# PanelDue.net
KiCad netlist of a schematic drawn in EAGLE
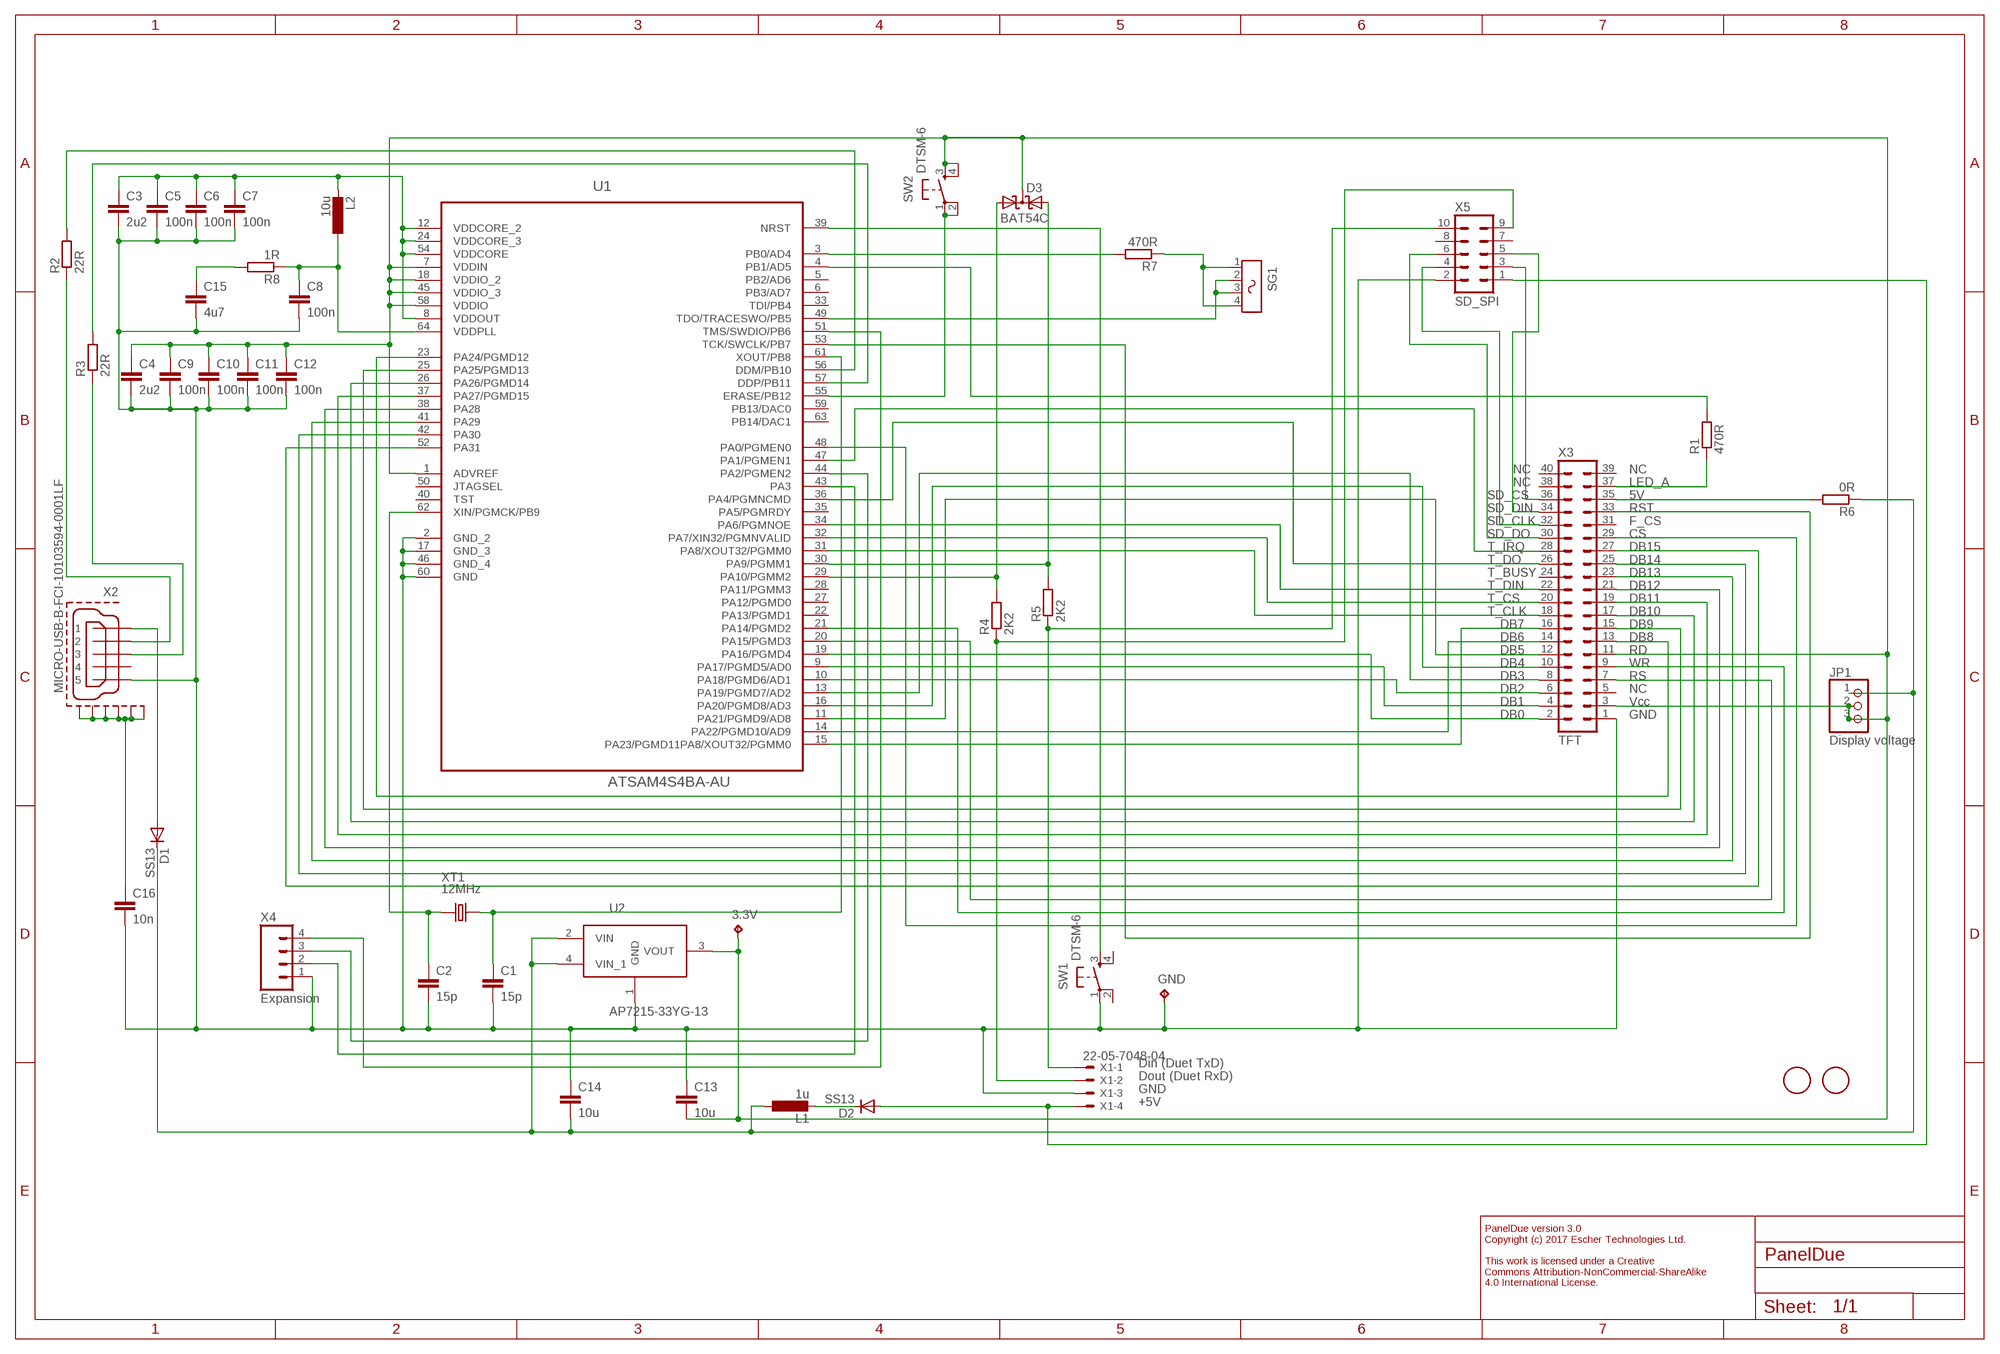
[diagram p0: schematic, sheet 1]

(export (version "E")
  (design (tool "Eeschema 10.0.6"))
  (components
    (comp (ref "3.3V")
      (value "TPPAD1-10")
      (footprint "eagle-import:P1-10")
      (libsource (lib "eagle-import") (part "TPPAD1-10"))
    )
    (comp (ref "C1")
      (value "15p")
      (footprint "eagle-import:C0603")
      (libsource (lib "eagle-import") (part "C-EUC0603"))
    )
    (comp (ref "C2")
      (value "15p")
      (footprint "eagle-import:C0603")
      (libsource (lib "eagle-import") (part "C-EUC0603"))
    )
    (comp (ref "C3")
      (value "2u2")
      (footprint "eagle-import:C0603")
      (libsource (lib "eagle-import") (part "C-EUC0603"))
    )
    (comp (ref "C4")
      (value "2u2")
      (footprint "eagle-import:C0603")
      (libsource (lib "eagle-import") (part "C-EUC0603"))
    )
    (comp (ref "C5")
      (value "100n")
      (footprint "eagle-import:C0603")
      (libsource (lib "eagle-import") (part "C-EUC0603"))
    )
    (comp (ref "C6")
      (value "100n")
      (footprint "eagle-import:C0603")
      (libsource (lib "eagle-import") (part "C-EUC0603"))
    )
    (comp (ref "C7")
      (value "100n")
      (footprint "eagle-import:C0603")
      (libsource (lib "eagle-import") (part "C-EUC0603"))
    )
    (comp (ref "C8")
      (value "100n")
      (footprint "eagle-import:C0603")
      (libsource (lib "eagle-import") (part "C-EUC0603"))
    )
    (comp (ref "C9")
      (value "100n")
      (footprint "eagle-import:C0603")
      (libsource (lib "eagle-import") (part "C-EUC0603"))
    )
    (comp (ref "C10")
      (value "100n")
      (footprint "eagle-import:C0603")
      (libsource (lib "eagle-import") (part "C-EUC0603"))
    )
    (comp (ref "C11")
      (value "100n")
      (footprint "eagle-import:C0603")
      (libsource (lib "eagle-import") (part "C-EUC0603"))
    )
    (comp (ref "C12")
      (value "100n")
      (footprint "eagle-import:C0603")
      (libsource (lib "eagle-import") (part "C-EUC0603"))
    )
    (comp (ref "C13")
      (value "10u")
      (footprint "eagle-import:C0805")
      (libsource (lib "eagle-import") (part "C-EUC0805"))
    )
    (comp (ref "C14")
      (value "10u")
      (footprint "eagle-import:C0805")
      (libsource (lib "eagle-import") (part "C-EUC0805"))
    )
    (comp (ref "C15")
      (value "4u7")
      (footprint "eagle-import:C0603")
      (libsource (lib "eagle-import") (part "C-EUC0603"))
    )
    (comp (ref "C16")
      (value "10n")
      (footprint "eagle-import:C0603")
      (libsource (lib "eagle-import") (part "C-EUC0603"))
    )
    (comp (ref "D1")
      (value "SS13")
      (footprint "eagle-import:DO214AC")
      (libsource (lib "eagle-import") (part "DIODE-DO214AC"))
    )
    (comp (ref "D2")
      (value "SS13")
      (footprint "eagle-import:DO214AC")
      (libsource (lib "eagle-import") (part "DIODE-DO214AC"))
    )
    (comp (ref "D3")
      (value "BAT54C")
      (footprint "eagle-import:SOT23")
      (libsource (lib "eagle-import") (part "BAT54C"))
    )
    (comp (ref "GND")
      (value "TPPAD1-10")
      (footprint "eagle-import:P1-10")
      (libsource (lib "eagle-import") (part "TPPAD1-10"))
    )
    (comp (ref "JP1")
      (value "Display voltage")
      (footprint "eagle-import:1X03")
      (libsource (lib "eagle-import") (part "PINHD-1X3"))
    )
    (comp (ref "L1")
      (value "1u")
      (footprint "eagle-import:L2012C")
      (libsource (lib "eagle-import") (part "L-EUL2012C"))
    )
    (comp (ref "L2")
      (value "10u")
      (footprint "eagle-import:L2012C")
      (libsource (lib "eagle-import") (part "L-EUL2012C"))
    )
    (comp (ref "R1")
      (value "470R")
      (footprint "eagle-import:R0603")
      (libsource (lib "eagle-import") (part "R-EU_R0603"))
    )
    (comp (ref "R2")
      (value "22R")
      (footprint "eagle-import:R0603")
      (libsource (lib "eagle-import") (part "R-EU_R0603"))
    )
    (comp (ref "R3")
      (value "22R")
      (footprint "eagle-import:R0603")
      (libsource (lib "eagle-import") (part "R-EU_R0603"))
    )
    (comp (ref "R4")
      (value "2K2")
      (footprint "eagle-import:R0603")
      (libsource (lib "eagle-import") (part "R-EU_R0603"))
    )
    (comp (ref "R5")
      (value "2K2")
      (footprint "eagle-import:R0603")
      (libsource (lib "eagle-import") (part "R-EU_R0603"))
    )
    (comp (ref "R6")
      (value "0R")
      (footprint "eagle-import:R0603")
      (libsource (lib "eagle-import") (part "R-EU_R0603"))
    )
    (comp (ref "R7")
      (value "470R")
      (footprint "eagle-import:R0603")
      (libsource (lib "eagle-import") (part "R-EU_R0603"))
    )
    (comp (ref "R8")
      (value "1R")
      (footprint "eagle-import:R0603")
      (libsource (lib "eagle-import") (part "R-EU_R0603"))
    )
    (comp (ref "SG1")
      (value "F/QMX2")
      (footprint "eagle-import:F_QMX2")
      (libsource (lib "eagle-import") (part "F/QMX2"))
    )
    (comp (ref "SW1")
      (value "DTSM-6")
      (footprint "eagle-import:DTSM-6")
      (libsource (lib "eagle-import") (part "DTSM-6"))
    )
    (comp (ref "SW2")
      (value "DTSM-6")
      (footprint "eagle-import:DTSM-6")
      (libsource (lib "eagle-import") (part "DTSM-6"))
    )
    (comp (ref "U$1")
      (value "FIDUCIAL")
      (footprint "eagle-import:FIDUCIAL_1MM")
      (libsource (lib "eagle-import") (part "FIDUCIAL"))
    )
    (comp (ref "U$2")
      (value "FIDUCIAL")
      (footprint "eagle-import:FIDUCIAL_1MM")
      (libsource (lib "eagle-import") (part "FIDUCIAL"))
    )
    (comp (ref "U1")
      (value "ATSAM4S4BA-AU")
      (footprint "eagle-import:QFP50P1200X1200X160-64N")
      (fields (field (name "MPN") "ATSAM3S2BA-AU"))
      (libsource (lib "eagle-import") (part "ATSAM3S2BA-AU"))
    )
    (comp (ref "U2")
      (value "AP7215-33YG-13")
      (footprint "eagle-import:SOT150P400X160-4N")
      (fields (field (name "MPN") "MCP1702T-3302E/MB"))
      (libsource (lib "eagle-import") (part "MCP17-MCP1702T-3302E/MB"))
    )
    (comp (ref "X1")
      (value "22-05-7048-04")
      (footprint "eagle-import:7395-04")
      (libsource (lib "eagle-import") (part "22-?-0405-7048"))
    )
    (comp (ref "X2")
      (value "MICRO-USB-B-FCI-10103594-0001LF")
      (footprint "eagle-import:10103594-0001LF")
      (libsource (lib "eagle-import") (part "MICRO-USB-B-FCI-10103594-0001LF"))
    )
    (comp (ref "X3")
      (value "TFT")
      (footprint "eagle-import:MA20-2")
      (libsource (lib "eagle-import") (part "MA20-2"))
    )
    (comp (ref "X4")
      (value "Expansion")
      (footprint "eagle-import:1X04")
      (libsource (lib "eagle-import") (part "M04PTH"))
    )
    (comp (ref "X5")
      (value "SD_SPI")
      (footprint "eagle-import:ML10L")
      (libsource (lib "eagle-import") (part "ML10L"))
    )
    (comp (ref "XT1")
      (value "12MHz")
      (footprint "eagle-import:CRYSTAL-SMD-2PIN-5X3.2")
      (libsource (lib "eagle-import") (part "CRYSTAL-SMD-2PIN-5X3.2"))
    )
  )
  (nets
    (net (code "1") (name "Net-(C15-Pad1)") (class "Default")
      (node (ref "C15") (pin "1") (pinfunction "1_1") (pintype "passive"))
      (node (ref "R8") (pin "2") (pinfunction "2_2") (pintype "passive"))
    )
    (net (code "2") (name "Net-(C16-Pad1)") (class "Default")
      (node (ref "C16") (pin "1") (pinfunction "1_1") (pintype "passive"))
      (node (ref "X2") (pin "GND1") (pinfunction "GND1_GND1") (pintype "bidirectional"))
      (node (ref "X2") (pin "GND2") (pinfunction "GND2_GND2") (pintype "bidirectional"))
      (node (ref "X2") (pin "GND3") (pinfunction "GND3_GND3") (pintype "bidirectional"))
      (node (ref "X2") (pin "GND4") (pinfunction "GND4_GND4") (pintype "bidirectional"))
      (node (ref "X2") (pin "GND5") (pinfunction "GND5_GND5") (pintype "bidirectional"))
      (node (ref "X2") (pin "GND6") (pinfunction "GND6_GND6") (pintype "bidirectional"))
    )
    (net (code "3") (name "Net-(D1-PadA)") (class "Default")
      (node (ref "D1") (pin "A") (pinfunction "A_A") (pintype "passive"))
      (node (ref "X2") (pin "1") (pinfunction "1_1") (pintype "input"))
    )
    (net (code "4") (name "Net-(D2-PadC)") (class "Default")
      (node (ref "D2") (pin "C") (pinfunction "C_C") (pintype "passive"))
      (node (ref "L1") (pin "2") (pinfunction "2_2") (pintype "passive"))
    )
    (net (code "5") (name "Net-(D3-A1)") (class "Default")
      (node (ref "D3") (pin "1") (pinfunction "A1_1") (pintype "passive"))
      (node (ref "R4") (pin "2") (pinfunction "2_2") (pintype "passive"))
      (node (ref "U1") (pin "29") (pinfunction "PA10/PGMM2_29") (pintype "bidirectional"))
    )
    (net (code "6") (name "Net-(D3-A2)") (class "Default")
      (node (ref "D3") (pin "2") (pinfunction "A2_2") (pintype "passive"))
      (node (ref "R5") (pin "2") (pinfunction "2_2") (pintype "passive"))
      (node (ref "U1") (pin "30") (pinfunction "PA9/PGMM1_30") (pintype "bidirectional"))
    )
    (net (code "7") (name "Net-(D3-CC)") (class "Default")
      (node (ref "3.3V") (pin "TP") (pinfunction "TP_TP") (pintype "input"))
      (node (ref "C10") (pin "1") (pinfunction "1_1") (pintype "passive"))
      (node (ref "C11") (pin "1") (pinfunction "1_1") (pintype "passive"))
      (node (ref "C12") (pin "1") (pinfunction "1_1") (pintype "passive"))
      (node (ref "C13") (pin "2") (pinfunction "2_2") (pintype "passive"))
      (node (ref "C4") (pin "1") (pinfunction "1_1") (pintype "passive"))
      (node (ref "C9") (pin "1") (pinfunction "1_1") (pintype "passive"))
      (node (ref "D3") (pin "3") (pinfunction "CC_3") (pintype "passive"))
      (node (ref "JP1") (pin "2") (pinfunction "2_2") (pintype "passive"))
      (node (ref "JP1") (pin "3") (pinfunction "3_3") (pintype "passive"))
      (node (ref "SW2") (pin "3") (pinfunction "3_3") (pintype "passive"))
      (node (ref "SW2") (pin "4") (pinfunction "4_4") (pintype "passive"))
      (node (ref "U1") (pin "1") (pinfunction "ADVREF_1") (pintype "input"))
      (node (ref "U1") (pin "18") (pinfunction "VDDIO_2_18") (pintype "power_in"))
      (node (ref "U1") (pin "45") (pinfunction "VDDIO_3_45") (pintype "power_in"))
      (node (ref "U1") (pin "58") (pinfunction "VDDIO_58") (pintype "power_in"))
      (node (ref "U1") (pin "7") (pinfunction "VDDIN_7") (pintype "power_in"))
      (node (ref "U2") (pin "3") (pinfunction "VOUT_3") (pintype "output"))
      (node (ref "X3") (pin "11") (pinfunction "11_11") (pintype "passive"))
      (node (ref "X3") (pin "3") (pinfunction "3_3") (pintype "passive"))
    )
    (net (code "8") (name "Net-(R1-Pad1)") (class "Default")
      (node (ref "R1") (pin "1") (pinfunction "1_1") (pintype "passive"))
      (node (ref "X3") (pin "37") (pinfunction "37_37") (pintype "passive"))
    )
    (net (code "9") (name "Net-(R2-Pad1)") (class "Default")
      (node (ref "R2") (pin "1") (pinfunction "1_1") (pintype "passive"))
      (node (ref "X2") (pin "2") (pinfunction "2_2") (pintype "input"))
    )
    (net (code "10") (name "Net-(R3-Pad1)") (class "Default")
      (node (ref "R3") (pin "1") (pinfunction "1_1") (pintype "passive"))
      (node (ref "X2") (pin "3") (pinfunction "3_3") (pintype "input"))
    )
    (net (code "11") (name "Net-(R6-Pad2)") (class "Default")
      (node (ref "R6") (pin "2") (pinfunction "2_2") (pintype "passive"))
      (node (ref "X3") (pin "35") (pinfunction "35_35") (pintype "passive"))
    )
    (net (code "12") (name "Net-(SG1-P$1)") (class "Default")
      (node (ref "R7") (pin "1") (pinfunction "1_1") (pintype "passive"))
      (node (ref "SG1") (pin "1") (pinfunction "P$1_1") (pintype "input"))
      (node (ref "SG1") (pin "4") (pinfunction "P$4_4") (pintype "input"))
    )
    (net (code "13") (name "Net-(SG1-P$2)") (class "Default")
      (node (ref "SG1") (pin "2") (pinfunction "P$2_2") (pintype "input"))
      (node (ref "SG1") (pin "3") (pinfunction "P$3_3") (pintype "input"))
      (node (ref "U1") (pin "49") (pinfunction "TDO/TRACESWO/PB5_49") (pintype "bidirectional"))
    )
    (net (code "14") (name "Net-(U1-DDM{slash}PB10)") (class "Default")
      (node (ref "R2") (pin "2") (pinfunction "2_2") (pintype "passive"))
      (node (ref "U1") (pin "56") (pinfunction "DDM/PB10_56") (pintype "bidirectional"))
    )
    (net (code "15") (name "Net-(U1-DDP{slash}PB11)") (class "Default")
      (node (ref "R3") (pin "2") (pinfunction "2_2") (pintype "passive"))
      (node (ref "U1") (pin "57") (pinfunction "DDP/PB11_57") (pintype "bidirectional"))
    )
    (net (code "16") (name "Net-(U1-ERASE{slash}PB12)") (class "Default")
      (node (ref "SW2") (pin "1") (pinfunction "1_1") (pintype "passive"))
      (node (ref "SW2") (pin "2") (pinfunction "2_2") (pintype "passive"))
      (node (ref "U1") (pin "55") (pinfunction "ERASE/PB12_55") (pintype "bidirectional"))
    )
    (net (code "17") (name "Net-(U1-GND)") (class "Default")
      (node (ref "C1") (pin "2") (pinfunction "2_2") (pintype "passive"))
      (node (ref "C10") (pin "2") (pinfunction "2_2") (pintype "passive"))
      (node (ref "C11") (pin "2") (pinfunction "2_2") (pintype "passive"))
      (node (ref "C12") (pin "2") (pinfunction "2_2") (pintype "passive"))
      (node (ref "C13") (pin "1") (pinfunction "1_1") (pintype "passive"))
      (node (ref "C14") (pin "1") (pinfunction "1_1") (pintype "passive"))
      (node (ref "C15") (pin "2") (pinfunction "2_2") (pintype "passive"))
      (node (ref "C16") (pin "2") (pinfunction "2_2") (pintype "passive"))
      (node (ref "C2") (pin "2") (pinfunction "2_2") (pintype "passive"))
      (node (ref "C3") (pin "2") (pinfunction "2_2") (pintype "passive"))
      (node (ref "C4") (pin "2") (pinfunction "2_2") (pintype "passive"))
      (node (ref "C5") (pin "2") (pinfunction "2_2") (pintype "passive"))
      (node (ref "C6") (pin "2") (pinfunction "2_2") (pintype "passive"))
      (node (ref "C7") (pin "2") (pinfunction "2_2") (pintype "passive"))
      (node (ref "C8") (pin "2") (pinfunction "2_2") (pintype "passive"))
      (node (ref "C9") (pin "2") (pinfunction "2_2") (pintype "passive"))
      (node (ref "GND") (pin "TP") (pinfunction "TP_TP") (pintype "input"))
      (node (ref "SW1") (pin "1") (pinfunction "1_1") (pintype "passive"))
      (node (ref "U1") (pin "17") (pinfunction "GND_3_17") (pintype "passive"))
      (node (ref "U1") (pin "2") (pinfunction "GND_2_2") (pintype "passive"))
      (node (ref "U1") (pin "46") (pinfunction "GND_4_46") (pintype "passive"))
      (node (ref "U1") (pin "60") (pinfunction "GND_60") (pintype "passive"))
      (node (ref "U2") (pin "1") (pinfunction "GND_1") (pintype "power_in"))
      (node (ref "X1") (pin "3") (pinfunction "S_3") (pintype "passive"))
      (node (ref "X2") (pin "5") (pinfunction "5_5") (pintype "input"))
      (node (ref "X3") (pin "1") (pinfunction "1_1") (pintype "passive"))
      (node (ref "X4") (pin "1") (pinfunction "1_1") (pintype "passive"))
      (node (ref "X5") (pin "2") (pinfunction "2_2") (pintype "passive"))
    )
    (net (code "18") (name "Net-(U1-NRST)") (class "Default")
      (node (ref "SW1") (pin "3") (pinfunction "3_3") (pintype "passive"))
      (node (ref "U1") (pin "39") (pinfunction "NRST_39") (pintype "bidirectional"))
    )
    (net (code "19") (name "Net-(U1-PA0{slash}PGMEN0)") (class "Default")
      (node (ref "U1") (pin "48") (pinfunction "PA0/PGMEN0_48") (pintype "bidirectional"))
      (node (ref "X3") (pin "29") (pinfunction "29_29") (pintype "passive"))
    )
    (net (code "20") (name "Net-(U1-PA1{slash}PGMEN1)") (class "Default")
      (node (ref "U1") (pin "47") (pinfunction "PA1/PGMEN1_47") (pintype "bidirectional"))
      (node (ref "X3") (pin "28") (pinfunction "28_28") (pintype "passive"))
    )
    (net (code "21") (name "Net-(U1-PA2{slash}PGMEN2)") (class "Default")
      (node (ref "U1") (pin "44") (pinfunction "PA2/PGMEN2_44") (pintype "bidirectional"))
      (node (ref "X4") (pin "3") (pinfunction "3_3") (pintype "passive"))
    )
    (net (code "22") (name "Net-(U1-PA3)") (class "Default")
      (node (ref "U1") (pin "43") (pinfunction "PA3_43") (pintype "bidirectional"))
      (node (ref "X4") (pin "2") (pinfunction "2_2") (pintype "passive"))
    )
    (net (code "23") (name "Net-(U1-PA4{slash}PGMNCMD)") (class "Default")
      (node (ref "U1") (pin "36") (pinfunction "PA4/PGMNCMD_36") (pintype "bidirectional"))
      (node (ref "X3") (pin "26") (pinfunction "26_26") (pintype "passive"))
    )
    (net (code "24") (name "Net-(U1-PA6{slash}PGMNOE)") (class "Default")
      (node (ref "U1") (pin "34") (pinfunction "PA6/PGMNOE_34") (pintype "bidirectional"))
      (node (ref "X3") (pin "22") (pinfunction "22_22") (pintype "passive"))
    )
    (net (code "25") (name "Net-(U1-PA7{slash}XIN32{slash}PGMNVALID)") (class "Default")
      (node (ref "U1") (pin "32") (pinfunction "PA7/XIN32/PGMNVALID_32") (pintype "bidirectional"))
      (node (ref "X3") (pin "20") (pinfunction "20_20") (pintype "passive"))
    )
    (net (code "26") (name "Net-(U1-PA8{slash}XOUT32{slash}PGMM0)") (class "Default")
      (node (ref "U1") (pin "31") (pinfunction "PA8/XOUT32/PGMM0_31") (pintype "bidirectional"))
      (node (ref "X3") (pin "18") (pinfunction "18_18") (pintype "passive"))
    )
    (net (code "27") (name "Net-(U1-PA14{slash}PGMD2)") (class "Default")
      (node (ref "U1") (pin "21") (pinfunction "PA14/PGMD2_21") (pintype "bidirectional"))
      (node (ref "X3") (pin "9") (pinfunction "9_9") (pintype "passive"))
    )
    (net (code "28") (name "Net-(U1-PA15{slash}PGMD3)") (class "Default")
      (node (ref "U1") (pin "20") (pinfunction "PA15/PGMD3_20") (pintype "bidirectional"))
      (node (ref "X3") (pin "7") (pinfunction "7_7") (pintype "passive"))
    )
    (net (code "29") (name "Net-(U1-PA16{slash}PGMD4)") (class "Default")
      (node (ref "U1") (pin "19") (pinfunction "PA16/PGMD4_19") (pintype "bidirectional"))
      (node (ref "X3") (pin "2") (pinfunction "2_2") (pintype "passive"))
    )
    (net (code "30") (name "Net-(U1-PA17{slash}PGMD5{slash}AD0)") (class "Default")
      (node (ref "U1") (pin "9") (pinfunction "PA17/PGMD5/AD0_9") (pintype "bidirectional"))
      (node (ref "X3") (pin "4") (pinfunction "4_4") (pintype "passive"))
    )
    (net (code "31") (name "Net-(U1-PA18{slash}PGMD6{slash}AD1)") (class "Default")
      (node (ref "U1") (pin "10") (pinfunction "PA18/PGMD6/AD1_10") (pintype "bidirectional"))
      (node (ref "X3") (pin "6") (pinfunction "6_6") (pintype "passive"))
    )
    (net (code "32") (name "Net-(U1-PA19{slash}PGMD7{slash}AD2)") (class "Default")
      (node (ref "U1") (pin "13") (pinfunction "PA19/PGMD7/AD2_13") (pintype "bidirectional"))
      (node (ref "X3") (pin "8") (pinfunction "8_8") (pintype "passive"))
    )
    (net (code "33") (name "Net-(U1-PA20{slash}PGMD8{slash}AD3)") (class "Default")
      (node (ref "U1") (pin "16") (pinfunction "PA20/PGMD8/AD3_16") (pintype "bidirectional"))
      (node (ref "X3") (pin "10") (pinfunction "10_10") (pintype "passive"))
    )
    (net (code "34") (name "Net-(U1-PA21{slash}PGMD9{slash}AD8)") (class "Default")
      (node (ref "U1") (pin "11") (pinfunction "PA21/PGMD9/AD8_11") (pintype "bidirectional"))
      (node (ref "X3") (pin "12") (pinfunction "12_12") (pintype "passive"))
    )
    (net (code "35") (name "Net-(U1-PA22{slash}PGMD10{slash}AD9)") (class "Default")
      (node (ref "U1") (pin "14") (pinfunction "PA22/PGMD10/AD9_14") (pintype "bidirectional"))
      (node (ref "X3") (pin "14") (pinfunction "14_14") (pintype "passive"))
    )
    (net (code "36") (name "Net-(U1-PA23{slash}PGMD11PA8{slash}XOUT32{slash}PGMM0)") (class "Default")
      (node (ref "U1") (pin "15") (pinfunction "PA23/PGMD11PA8/XOUT32/PGMM0_15") (pintype "bidirectional"))
      (node (ref "X3") (pin "16") (pinfunction "16_16") (pintype "passive"))
    )
    (net (code "37") (name "Net-(U1-PA24{slash}PGMD12)") (class "Default")
      (node (ref "U1") (pin "23") (pinfunction "PA24/PGMD12_23") (pintype "bidirectional"))
      (node (ref "X3") (pin "13") (pinfunction "13_13") (pintype "passive"))
    )
    (net (code "38") (name "Net-(U1-PA25{slash}PGMD13)") (class "Default")
      (node (ref "U1") (pin "25") (pinfunction "PA25/PGMD13_25") (pintype "bidirectional"))
      (node (ref "X3") (pin "15") (pinfunction "15_15") (pintype "passive"))
    )
    (net (code "39") (name "Net-(U1-PA26{slash}PGMD14)") (class "Default")
      (node (ref "U1") (pin "26") (pinfunction "PA26/PGMD14_26") (pintype "bidirectional"))
      (node (ref "X3") (pin "17") (pinfunction "17_17") (pintype "passive"))
    )
    (net (code "40") (name "Net-(U1-PA27{slash}PGMD15)") (class "Default")
      (node (ref "U1") (pin "37") (pinfunction "PA27/PGMD15_37") (pintype "bidirectional"))
      (node (ref "X3") (pin "19") (pinfunction "19_19") (pintype "passive"))
    )
    (net (code "41") (name "Net-(U1-PA28)") (class "Default")
      (node (ref "U1") (pin "38") (pinfunction "PA28_38") (pintype "bidirectional"))
      (node (ref "X3") (pin "21") (pinfunction "21_21") (pintype "passive"))
    )
    (net (code "42") (name "Net-(U1-PA29)") (class "Default")
      (node (ref "U1") (pin "41") (pinfunction "PA29_41") (pintype "bidirectional"))
      (node (ref "X3") (pin "23") (pinfunction "23_23") (pintype "passive"))
    )
    (net (code "43") (name "Net-(U1-PA30)") (class "Default")
      (node (ref "U1") (pin "42") (pinfunction "PA30_42") (pintype "bidirectional"))
      (node (ref "X3") (pin "25") (pinfunction "25_25") (pintype "passive"))
    )
    (net (code "44") (name "Net-(U1-PA31)") (class "Default")
      (node (ref "U1") (pin "52") (pinfunction "PA31_52") (pintype "bidirectional"))
      (node (ref "X3") (pin "27") (pinfunction "27_27") (pintype "passive"))
    )
    (net (code "45") (name "Net-(U1-PB0{slash}AD4)") (class "Default")
      (node (ref "R7") (pin "2") (pinfunction "2_2") (pintype "passive"))
      (node (ref "U1") (pin "3") (pinfunction "PB0/AD4_3") (pintype "bidirectional"))
    )
    (net (code "46") (name "Net-(U1-PB1{slash}AD5)") (class "Default")
      (node (ref "R1") (pin "2") (pinfunction "2_2") (pintype "passive"))
      (node (ref "U1") (pin "4") (pinfunction "PB1/AD5_4") (pintype "bidirectional"))
    )
    (net (code "47") (name "Net-(U1-TCK{slash}SWCLK{slash}PB7)") (class "Default")
      (node (ref "U1") (pin "53") (pinfunction "TCK/SWCLK/PB7_53") (pintype "bidirectional"))
      (node (ref "X3") (pin "33") (pinfunction "33_33") (pintype "passive"))
    )
    (net (code "48") (name "Net-(U1-TMS{slash}SWDIO{slash}PB6)") (class "Default")
      (node (ref "U1") (pin "51") (pinfunction "TMS/SWDIO/PB6_51") (pintype "bidirectional"))
      (node (ref "X4") (pin "4") (pinfunction "4_4") (pintype "passive"))
    )
    (net (code "49") (name "Net-(U1-VDDCORE)") (class "Default")
      (node (ref "C3") (pin "1") (pinfunction "1_1") (pintype "passive"))
      (node (ref "C5") (pin "1") (pinfunction "1_1") (pintype "passive"))
      (node (ref "C6") (pin "1") (pinfunction "1_1") (pintype "passive"))
      (node (ref "C7") (pin "1") (pinfunction "1_1") (pintype "passive"))
      (node (ref "L2") (pin "2") (pinfunction "2_2") (pintype "passive"))
      (node (ref "U1") (pin "12") (pinfunction "VDDCORE_2_12") (pintype "power_in"))
      (node (ref "U1") (pin "24") (pinfunction "VDDCORE_3_24") (pintype "power_in"))
      (node (ref "U1") (pin "54") (pinfunction "VDDCORE_54") (pintype "power_in"))
      (node (ref "U1") (pin "8") (pinfunction "VDDOUT_8") (pintype "power_in"))
    )
    (net (code "50") (name "Net-(U1-VDDPLL)") (class "Default")
      (node (ref "C8") (pin "1") (pinfunction "1_1") (pintype "passive"))
      (node (ref "L2") (pin "1") (pinfunction "1_1") (pintype "passive"))
      (node (ref "R8") (pin "1") (pinfunction "1_1") (pintype "passive"))
      (node (ref "U1") (pin "64") (pinfunction "VDDPLL_64") (pintype "power_in"))
    )
    (net (code "51") (name "Net-(U1-XIN{slash}PGMCK{slash}PB9)") (class "Default")
      (node (ref "C2") (pin "1") (pinfunction "1_1") (pintype "passive"))
      (node (ref "U1") (pin "62") (pinfunction "XIN/PGMCK/PB9_62") (pintype "input"))
      (node (ref "XT1") (pin "P$1") (pinfunction "1_P$1") (pintype "passive"))
    )
    (net (code "52") (name "Net-(U1-XOUT{slash}PB8)") (class "Default")
      (node (ref "C1") (pin "1") (pinfunction "1_1") (pintype "passive"))
      (node (ref "U1") (pin "61") (pinfunction "XOUT/PB8_61") (pintype "output"))
      (node (ref "XT1") (pin "P$2") (pinfunction "2_P$2") (pintype "passive"))
    )
    (net (code "53") (name "Net-(U2-VIN)") (class "Default")
      (node (ref "C14") (pin "2") (pinfunction "2_2") (pintype "passive"))
      (node (ref "D1") (pin "C") (pinfunction "C_C") (pintype "passive"))
      (node (ref "JP1") (pin "1") (pinfunction "1_1") (pintype "passive"))
      (node (ref "L1") (pin "1") (pinfunction "1_1") (pintype "passive"))
      (node (ref "R6") (pin "1") (pinfunction "1_1") (pintype "passive"))
      (node (ref "U2") (pin "2") (pinfunction "VIN_2") (pintype "input"))
      (node (ref "U2") (pin "4") (pinfunction "VIN_1_4") (pintype "input"))
    )
    (net (code "54") (name "Net-(X1A-S)") (class "Default")
      (node (ref "R5") (pin "1") (pinfunction "1_1") (pintype "passive"))
      (node (ref "X1") (pin "1") (pinfunction "S_1") (pintype "passive"))
      (node (ref "X5") (pin "10") (pinfunction "10_10") (pintype "passive"))
    )
    (net (code "55") (name "Net-(X1B-S)") (class "Default")
      (node (ref "R4") (pin "1") (pinfunction "1_1") (pintype "passive"))
      (node (ref "X1") (pin "2") (pinfunction "S_2") (pintype "passive"))
      (node (ref "X5") (pin "9") (pinfunction "9_9") (pintype "passive"))
    )
    (net (code "56") (name "Net-(X1D-S)") (class "Default")
      (node (ref "D2") (pin "A") (pinfunction "A_A") (pintype "passive"))
      (node (ref "X1") (pin "4") (pinfunction "S_4") (pintype "passive"))
      (node (ref "X5") (pin "1") (pinfunction "1_1") (pintype "passive"))
    )
    (net (code "57") (name "Net-(X3-Pad30)") (class "Default")
      (node (ref "X3") (pin "30") (pinfunction "30_30") (pintype "passive"))
      (node (ref "X5") (pin "6") (pinfunction "6_6") (pintype "passive"))
    )
    (net (code "58") (name "Net-(X3-Pad32)") (class "Default")
      (node (ref "X3") (pin "32") (pinfunction "32_32") (pintype "passive"))
      (node (ref "X5") (pin "4") (pinfunction "4_4") (pintype "passive"))
    )
    (net (code "59") (name "Net-(X3-Pad34)") (class "Default")
      (node (ref "X3") (pin "34") (pinfunction "34_34") (pintype "passive"))
      (node (ref "X5") (pin "5") (pinfunction "5_5") (pintype "passive"))
    )
    (net (code "60") (name "Net-(X3-Pad36)") (class "Default")
      (node (ref "X3") (pin "36") (pinfunction "36_36") (pintype "passive"))
      (node (ref "X5") (pin "3") (pinfunction "3_3") (pintype "passive"))
    )
    (net (code "61") (name "unconnected-(SW1-Pad2)") (class "Default")
      (node (ref "SW1") (pin "2") (pinfunction "2_2") (pintype "passive"))
    )
    (net (code "62") (name "unconnected-(SW1-Pad4)") (class "Default")
      (node (ref "SW1") (pin "4") (pinfunction "4_4") (pintype "passive"))
    )
    (net (code "63") (name "unconnected-(U1-JTAGSEL-Pad50)") (class "Default")
      (node (ref "U1") (pin "50") (pinfunction "JTAGSEL_50") (pintype "input"))
    )
    (net (code "64") (name "unconnected-(U1-PA5{slash}PGMRDY-Pad35)") (class "Default")
      (node (ref "U1") (pin "35") (pinfunction "PA5/PGMRDY_35") (pintype "bidirectional"))
    )
    (net (code "65") (name "unconnected-(U1-PA11{slash}PGMM3-Pad28)") (class "Default")
      (node (ref "U1") (pin "28") (pinfunction "PA11/PGMM3_28") (pintype "bidirectional"))
    )
    (net (code "66") (name "unconnected-(U1-PA12{slash}PGMD0-Pad27)") (class "Default")
      (node (ref "U1") (pin "27") (pinfunction "PA12/PGMD0_27") (pintype "bidirectional"))
    )
    (net (code "67") (name "unconnected-(U1-PA13{slash}PGMD1-Pad22)") (class "Default")
      (node (ref "U1") (pin "22") (pinfunction "PA13/PGMD1_22") (pintype "bidirectional"))
    )
    (net (code "68") (name "unconnected-(U1-PB2{slash}AD6-Pad5)") (class "Default")
      (node (ref "U1") (pin "5") (pinfunction "PB2/AD6_5") (pintype "bidirectional"))
    )
    (net (code "69") (name "unconnected-(U1-PB3{slash}AD7-Pad6)") (class "Default")
      (node (ref "U1") (pin "6") (pinfunction "PB3/AD7_6") (pintype "bidirectional"))
    )
    (net (code "70") (name "unconnected-(U1-PB13{slash}DAC0-Pad59)") (class "Default")
      (node (ref "U1") (pin "59") (pinfunction "PB13/DAC0_59") (pintype "bidirectional"))
    )
    (net (code "71") (name "unconnected-(U1-PB14{slash}DAC1-Pad63)") (class "Default")
      (node (ref "U1") (pin "63") (pinfunction "PB14/DAC1_63") (pintype "bidirectional"))
    )
    (net (code "72") (name "unconnected-(U1-TDI{slash}PB4-Pad33)") (class "Default")
      (node (ref "U1") (pin "33") (pinfunction "TDI/PB4_33") (pintype "bidirectional"))
    )
    (net (code "73") (name "unconnected-(U1-TST-Pad40)") (class "Default")
      (node (ref "U1") (pin "40") (pinfunction "TST_40") (pintype "input"))
    )
    (net (code "74") (name "unconnected-(X2-Pad4)") (class "Default")
      (node (ref "X2") (pin "4") (pinfunction "4_4") (pintype "input"))
    )
    (net (code "75") (name "unconnected-(X3-Pad5)") (class "Default")
      (node (ref "X3") (pin "5") (pinfunction "5_5") (pintype "passive"))
    )
    (net (code "76") (name "unconnected-(X3-Pad24)") (class "Default")
      (node (ref "X3") (pin "24") (pinfunction "24_24") (pintype "passive"))
    )
    (net (code "77") (name "unconnected-(X3-Pad31)") (class "Default")
      (node (ref "X3") (pin "31") (pinfunction "31_31") (pintype "passive"))
    )
    (net (code "78") (name "unconnected-(X3-Pad38)") (class "Default")
      (node (ref "X3") (pin "38") (pinfunction "38_38") (pintype "passive"))
    )
    (net (code "79") (name "unconnected-(X3-Pad39)") (class "Default")
      (node (ref "X3") (pin "39") (pinfunction "39_39") (pintype "passive"))
    )
    (net (code "80") (name "unconnected-(X3-Pad40)") (class "Default")
      (node (ref "X3") (pin "40") (pinfunction "40_40") (pintype "passive"))
    )
    (net (code "81") (name "unconnected-(X5-Pad7)") (class "Default")
      (node (ref "X5") (pin "7") (pinfunction "7_7") (pintype "passive"))
    )
    (net (code "82") (name "unconnected-(X5-Pad8)") (class "Default")
      (node (ref "X5") (pin "8") (pinfunction "8_8") (pintype "passive"))
    )
  )
)
